# sos_v1.net
KiCad netlist of a schematic drawn in EAGLE
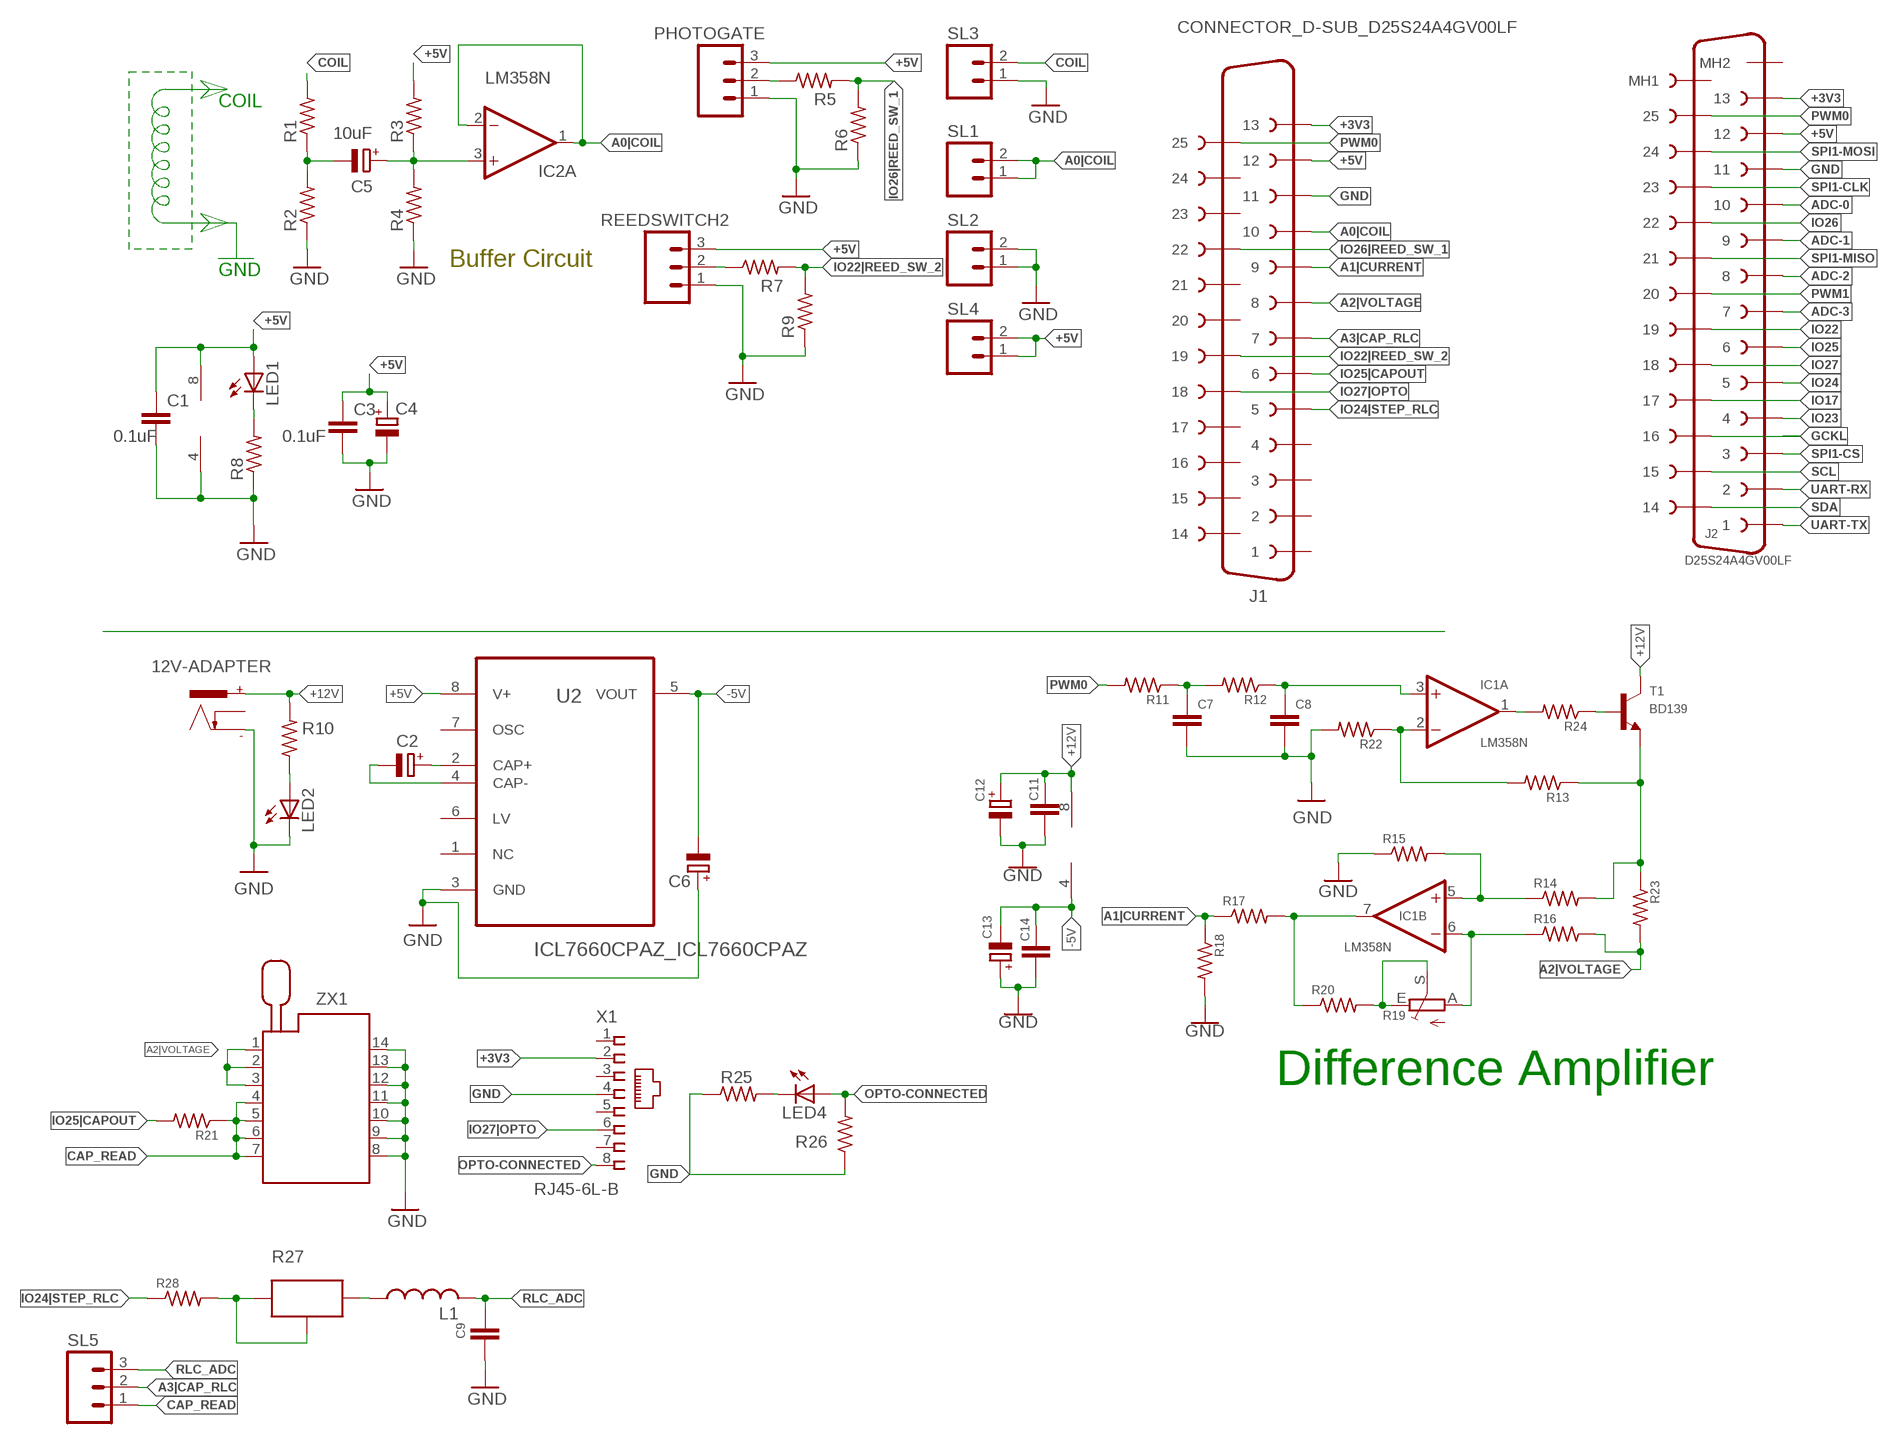
[diagram p0: schematic, sheet 1]

(export (version "E")
  (design (tool "Eeschema 10.0.6"))
  (components
    (comp (ref "12V-ADAPTER")
      (value "POWER_CON")
      (footprint "eagle-import:NEB21R")
      (libsource (lib "eagle-import") (part "POWER_CON"))
    )
    (comp (ref "C1")
      (value "0.1uF")
      (footprint "eagle-import:C025-025X050")
      (libsource (lib "eagle-import") (part "C-EU025-025X050"))
    )
    (comp (ref "C2")
      (value "CPOL-EUTT2D5")
      (footprint "eagle-import:TT2D5")
      (libsource (lib "eagle-import") (part "CPOL-EUTT2D5"))
    )
    (comp (ref "C3")
      (value "0.1uF")
      (footprint "eagle-import:C025-025X050")
      (libsource (lib "eagle-import") (part "C-EU025-025X050"))
    )
    (comp (ref "C4")
      (value "CPOL-EUE2.5-6")
      (footprint "eagle-import:E2,5-6")
      (libsource (lib "eagle-import") (part "CPOL-EUE2.5-6"))
    )
    (comp (ref "C5")
      (value "10uF")
      (footprint "eagle-import:E2,5-6")
      (libsource (lib "eagle-import") (part "CPOL-EUE2.5-6"))
    )
    (comp (ref "C6")
      (value "CPOL-EUTT2D5")
      (footprint "eagle-import:TT2D5")
      (libsource (lib "eagle-import") (part "CPOL-EUTT2D5"))
    )
    (comp (ref "C7")
      (value "C-EU025-025X050")
      (footprint "eagle-import:C025-025X050")
      (libsource (lib "eagle-import") (part "rcl_334_C-EU025-025X050"))
    )
    (comp (ref "C8")
      (value "C-EU025-025X050")
      (footprint "eagle-import:C025-025X050")
      (libsource (lib "eagle-import") (part "rcl_334_C-EU025-025X050"))
    )
    (comp (ref "C9")
      (value "C-EU025-025X050")
      (footprint "eagle-import:C025-025X050")
      (libsource (lib "eagle-import") (part "rcl_334_C-EU025-025X050"))
    )
    (comp (ref "C11")
      (value "C-EU025-025X050")
      (footprint "eagle-import:C025-025X050")
      (libsource (lib "eagle-import") (part "rcl_334_C-EU025-025X050"))
    )
    (comp (ref "C12")
      (value "CPOL-EUTT2D5")
      (footprint "eagle-import:TT2D5")
      (libsource (lib "eagle-import") (part "CPOL-EUTT2D5"))
    )
    (comp (ref "C13")
      (value "CPOL-EUTT2D5")
      (footprint "eagle-import:TT2D5")
      (libsource (lib "eagle-import") (part "CPOL-EUTT2D5"))
    )
    (comp (ref "C14")
      (value "C-EU025-025X050")
      (footprint "eagle-import:C025-025X050")
      (libsource (lib "eagle-import") (part "rcl_334_C-EU025-025X050"))
    )
    (comp (ref "IC1")
      (value "LM358N")
      (footprint "eagle-import:DIL08")
      (libsource (lib "eagle-import") (part "LM358N"))
    )
    (comp (ref "IC2")
      (value "LM358N")
      (footprint "eagle-import:DIL08")
      (libsource (lib "eagle-import") (part "LM358N"))
    )
    (comp (ref "J1")
      (value "CONNECTOR_D-SUB_D25S24A4GV00LF")
      (footprint "eagle-import:CONNECTOR_D-SUB_D25S24A4GV00LF")
      (fields (field (name "MANUFACTURER") "amphenol-icc") (field (name "MPN") "D25S24A4GV00LF"))
      (libsource (lib "eagle-import") (part "CONNECTOR_D-SUB_D25S24A4GV00LF"))
    )
    (comp (ref "J2")
      (value "D25S24A4GV00LF")
      (footprint "eagle-import:D25S24A4GV00LF")
      (fields (field (name "MANUFACTURER") "amphenol-icc"))
      (libsource (lib "eagle-import") (part "D25S24A4GV00LF"))
    )
    (comp (ref "L1")
      (value "L-USTJ3-U2")
      (footprint "eagle-import:TJ3-U2")
      (libsource (lib "eagle-import") (part "L-USTJ3-U2"))
    )
    (comp (ref "LED1")
      (value "LED3MM")
      (footprint "eagle-import:LED3MM")
      (libsource (lib "eagle-import") (part "LED3MM"))
    )
    (comp (ref "LED2")
      (value "LED3MM")
      (footprint "eagle-import:LED3MM")
      (libsource (lib "eagle-import") (part "LED3MM"))
    )
    (comp (ref "LED4")
      (value "LED3MM")
      (footprint "eagle-import:LED3MM")
      (libsource (lib "eagle-import") (part "LED3MM"))
    )
    (comp (ref "PHOTOGATE")
      (value "M03")
      (footprint "eagle-import:03P")
      (libsource (lib "eagle-import") (part "M03"))
    )
    (comp (ref "R1")
      (value "R-US_0204/7")
      (footprint "eagle-import:0204_7")
      (libsource (lib "eagle-import") (part "R-US_0204/7"))
    )
    (comp (ref "R2")
      (value "R-US_0204/7")
      (footprint "eagle-import:0204_7")
      (libsource (lib "eagle-import") (part "R-US_0204/7"))
    )
    (comp (ref "R3")
      (value "R-US_0204/7")
      (footprint "eagle-import:0204_7")
      (libsource (lib "eagle-import") (part "R-US_0204/7"))
    )
    (comp (ref "R4")
      (value "R-US_0204/7")
      (footprint "eagle-import:0204_7")
      (libsource (lib "eagle-import") (part "R-US_0204/7"))
    )
    (comp (ref "R5")
      (value "R-US_0204/7")
      (footprint "eagle-import:0204_7")
      (libsource (lib "eagle-import") (part "R-US_0204/7"))
    )
    (comp (ref "R6")
      (value "R-US_0204/7")
      (footprint "eagle-import:0204_7")
      (libsource (lib "eagle-import") (part "R-US_0204/7"))
    )
    (comp (ref "R7")
      (value "R-US_0204/7")
      (footprint "eagle-import:0204_7")
      (libsource (lib "eagle-import") (part "R-US_0204/7"))
    )
    (comp (ref "R8")
      (value "R-US_0204/7")
      (footprint "eagle-import:0204_7")
      (libsource (lib "eagle-import") (part "R-US_0204/7"))
    )
    (comp (ref "R9")
      (value "R-US_0204/7")
      (footprint "eagle-import:0204_7")
      (libsource (lib "eagle-import") (part "R-US_0204/7"))
    )
    (comp (ref "R10")
      (value "R-US_0204/7")
      (footprint "eagle-import:0204_7")
      (libsource (lib "eagle-import") (part "R-US_0204/7"))
    )
    (comp (ref "R11")
      (value "R-US_0204/7")
      (footprint "eagle-import:0204_7")
      (libsource (lib "eagle-import") (part "R-US_0204/7"))
    )
    (comp (ref "R12")
      (value "R-US_0204/7")
      (footprint "eagle-import:0204_7")
      (libsource (lib "eagle-import") (part "R-US_0204/7"))
    )
    (comp (ref "R13")
      (value "R-US_0204/7")
      (footprint "eagle-import:0204_7")
      (libsource (lib "eagle-import") (part "R-US_0204/7"))
    )
    (comp (ref "R14")
      (value "R-US_0204/7")
      (footprint "eagle-import:0204_7")
      (libsource (lib "eagle-import") (part "R-US_0204/7"))
    )
    (comp (ref "R15")
      (value "R-US_0204/7")
      (footprint "eagle-import:0204_7")
      (libsource (lib "eagle-import") (part "R-US_0204/7"))
    )
    (comp (ref "R16")
      (value "R-US_0204/7")
      (footprint "eagle-import:0204_7")
      (libsource (lib "eagle-import") (part "R-US_0204/7"))
    )
    (comp (ref "R17")
      (value "R-US_0204/7")
      (footprint "eagle-import:0204_7")
      (libsource (lib "eagle-import") (part "R-US_0204/7"))
    )
    (comp (ref "R18")
      (value "R-US_0204/7")
      (footprint "eagle-import:0204_7")
      (libsource (lib "eagle-import") (part "R-US_0204/7"))
    )
    (comp (ref "R19")
      (value "TRIM_EU-RJ9W")
      (footprint "eagle-import:RJ9W")
      (libsource (lib "eagle-import") (part "TRIM_EU-RJ9W"))
    )
    (comp (ref "R20")
      (value "R-US_0204/7")
      (footprint "eagle-import:0204_7")
      (libsource (lib "eagle-import") (part "R-US_0204/7"))
    )
    (comp (ref "R21")
      (value "R-US_0204/7")
      (footprint "eagle-import:0204_7")
      (libsource (lib "eagle-import") (part "R-US_0204/7"))
    )
    (comp (ref "R22")
      (value "R-US_0204/7")
      (footprint "eagle-import:0204_7")
      (libsource (lib "eagle-import") (part "R-US_0204/7"))
    )
    (comp (ref "R23")
      (value "R-US_0207/10")
      (footprint "eagle-import:0207_10")
      (libsource (lib "eagle-import") (part "R-US_0207/10"))
    )
    (comp (ref "R24")
      (value "R-US_0204/7")
      (footprint "eagle-import:0204_7")
      (libsource (lib "eagle-import") (part "R-US_0204/7"))
    )
    (comp (ref "R25")
      (value "R-US_0204/7")
      (footprint "eagle-import:0204_7")
      (libsource (lib "eagle-import") (part "R-US_0204/7"))
    )
    (comp (ref "R26")
      (value "R-US_0204/7")
      (footprint "eagle-import:0204_7")
      (libsource (lib "eagle-import") (part "R-US_0204/7"))
    )
    (comp (ref "R27")
      (value "POTNORMAL")
      (footprint "eagle-import:RJ9W")
      (libsource (lib "eagle-import") (part "POTNORMAL"))
    )
    (comp (ref "R28")
      (value "R-US_0207/10")
      (footprint "eagle-import:0207_10")
      (libsource (lib "eagle-import") (part "R-US_0207/10"))
    )
    (comp (ref "REEDSWITCH2")
      (value "M03")
      (footprint "eagle-import:03P")
      (libsource (lib "eagle-import") (part "M03"))
    )
    (comp (ref "SL1")
      (value "M02")
      (footprint "eagle-import:02P")
      (libsource (lib "eagle-import") (part "M02"))
    )
    (comp (ref "SL2")
      (value "M02")
      (footprint "eagle-import:02P")
      (libsource (lib "eagle-import") (part "M02"))
    )
    (comp (ref "SL3")
      (value "M02")
      (footprint "eagle-import:02P")
      (libsource (lib "eagle-import") (part "M02"))
    )
    (comp (ref "SL4")
      (value "M02")
      (footprint "eagle-import:02P")
      (libsource (lib "eagle-import") (part "M02"))
    )
    (comp (ref "SL5")
      (value "M03")
      (footprint "eagle-import:03P")
      (libsource (lib "eagle-import") (part "M03"))
    )
    (comp (ref "T1")
      (value "BD139")
      (footprint "eagle-import:TO126")
      (libsource (lib "eagle-import") (part "BD139"))
    )
    (comp (ref "U2")
      (value "ICL7660CPAZ_ICL7660CPAZ")
      (footprint "eagle-import:ICL7660CPAZ_DIP254P762X533-8")
      (fields (field (name "MF") "Renesas Electronics") (field (name "MP") "ICL7660CPAZ"))
      (libsource (lib "eagle-import") (part "ICL7660CPAZ_ICL7660CPAZ"))
    )
    (comp (ref "X1")
      (value "RJ45-6L-B")
      (footprint "eagle-import:RJ45-NO-SHIELD")
      (libsource (lib "eagle-import") (part "RJ45-6L-B"))
    )
    (comp (ref "ZX1")
      (value "214-3339-00-0602J")
      (footprint "eagle-import:214-3339-00-0602J")
      (fields (field (name "MF") "3M"))
      (libsource (lib "eagle-import") (part "214-3339-00-0602J"))
    )
  )
  (nets
    (net (code "1") (name "+3V3") (class "Default")
      (node (ref "J1") (pin "P$13") (pinfunction "13_P$13") (pintype "passive"))
      (node (ref "J2") (pin "13") (pinfunction "13_13") (pintype "passive"))
      (node (ref "X1") (pin "2") (pinfunction "2_2") (pintype "passive"))
    )
    (net (code "2") (name "+5V") (class "Default")
      (node (ref "C1") (pin "1") (pinfunction "1_1") (pintype "passive"))
      (node (ref "C3") (pin "1") (pinfunction "1_1") (pintype "passive"))
      (node (ref "C4") (pin "+") (pinfunction "+_+") (pintype "passive"))
      (node (ref "IC2") (pin "8") (pinfunction "V+_8") (pintype "power_in"))
      (node (ref "J1") (pin "P$14") (pinfunction "12_P$14") (pintype "passive"))
      (node (ref "J2") (pin "12") (pinfunction "12_12") (pintype "passive"))
      (node (ref "LED1") (pin "A") (pinfunction "A_A") (pintype "passive"))
      (node (ref "PHOTOGATE") (pin "3") (pinfunction "3_3") (pintype "passive"))
      (node (ref "R3") (pin "2") (pinfunction "2_2") (pintype "passive"))
      (node (ref "REEDSWITCH2") (pin "3") (pinfunction "3_3") (pintype "passive"))
      (node (ref "SL4") (pin "1") (pinfunction "1_1") (pintype "passive"))
      (node (ref "SL4") (pin "2") (pinfunction "2_2") (pintype "passive"))
      (node (ref "U2") (pin "8") (pinfunction "V+_8") (pintype "power_in"))
    )
    (net (code "3") (name "+12V") (class "Default")
      (node (ref "12V-ADAPTER") (pin "+") (pinfunction "+_+") (pintype "passive"))
      (node (ref "C11") (pin "1") (pinfunction "1_1") (pintype "passive"))
      (node (ref "C12") (pin "+") (pinfunction "+_+") (pintype "passive"))
      (node (ref "IC1") (pin "8") (pinfunction "V+_8") (pintype "power_in"))
      (node (ref "R10") (pin "2") (pinfunction "2_2") (pintype "passive"))
      (node (ref "T1") (pin "2") (pinfunction "C_2") (pintype "passive"))
    )
    (net (code "4") (name "-5V") (class "Default")
      (node (ref "C13") (pin "-") (pinfunction "-_-") (pintype "passive"))
      (node (ref "C14") (pin "1") (pinfunction "1_1") (pintype "passive"))
      (node (ref "C6") (pin "-") (pinfunction "-_-") (pintype "passive"))
      (node (ref "IC1") (pin "4") (pinfunction "V-_4") (pintype "power_in"))
      (node (ref "U2") (pin "5") (pinfunction "VOUT_5") (pintype "output"))
    )
    (net (code "5") (name "/MH1") (class "Default")
      (node (ref "J2") (pin "MH1") (pinfunction "MH1_MH1") (pintype "power_in"))
    )
    (net (code "6") (name "/MH2") (class "Default")
      (node (ref "J2") (pin "MH2") (pinfunction "MH2_MH2") (pintype "power_in"))
    )
    (net (code "7") (name "A0|COIL") (class "Default")
      (node (ref "IC2") (pin "1") (pinfunction "OUT_1") (pintype "output"))
      (node (ref "IC2") (pin "2") (pinfunction "-IN_2") (pintype "input"))
      (node (ref "J1") (pin "P$16") (pinfunction "10_P$16") (pintype "passive"))
      (node (ref "SL1") (pin "1") (pinfunction "1_1") (pintype "passive"))
      (node (ref "SL1") (pin "2") (pinfunction "2_2") (pintype "passive"))
    )
    (net (code "8") (name "A1|CURRENT") (class "Default")
      (node (ref "J1") (pin "P$17") (pinfunction "9_P$17") (pintype "passive"))
      (node (ref "R17") (pin "1") (pinfunction "1_1") (pintype "passive"))
      (node (ref "R18") (pin "1") (pinfunction "1_1") (pintype "passive"))
    )
    (net (code "9") (name "A2|VOLTAGE") (class "Default")
      (node (ref "J1") (pin "P$18") (pinfunction "8_P$18") (pintype "passive"))
      (node (ref "R16") (pin "2") (pinfunction "2_2") (pintype "passive"))
      (node (ref "R23") (pin "2") (pinfunction "2_2") (pintype "passive"))
      (node (ref "ZX1") (pin "1") (pinfunction "1_1") (pintype "passive"))
      (node (ref "ZX1") (pin "2") (pinfunction "2_2") (pintype "passive"))
      (node (ref "ZX1") (pin "3") (pinfunction "3_3") (pintype "passive"))
    )
    (net (code "10") (name "A3|CAP_RLC") (class "Default")
      (node (ref "J1") (pin "P$19") (pinfunction "7_P$19") (pintype "passive"))
      (node (ref "SL5") (pin "2") (pinfunction "2_2") (pintype "passive"))
    )
    (net (code "11") (name "ADC-0") (class "Default")
      (node (ref "J2") (pin "10") (pinfunction "10_10") (pintype "passive"))
    )
    (net (code "12") (name "ADC-1") (class "Default")
      (node (ref "J2") (pin "9") (pinfunction "9_9") (pintype "passive"))
    )
    (net (code "13") (name "ADC-2") (class "Default")
      (node (ref "J2") (pin "8") (pinfunction "8_8") (pintype "passive"))
    )
    (net (code "14") (name "ADC-3") (class "Default")
      (node (ref "J2") (pin "7") (pinfunction "7_7") (pintype "passive"))
    )
    (net (code "15") (name "CAP_READ") (class "Default")
      (node (ref "R21") (pin "1") (pinfunction "1_1") (pintype "passive"))
      (node (ref "SL5") (pin "1") (pinfunction "1_1") (pintype "passive"))
      (node (ref "ZX1") (pin "4") (pinfunction "4_4") (pintype "passive"))
      (node (ref "ZX1") (pin "5") (pinfunction "5_5") (pintype "passive"))
      (node (ref "ZX1") (pin "6") (pinfunction "6_6") (pintype "passive"))
      (node (ref "ZX1") (pin "7") (pinfunction "7_7") (pintype "passive"))
    )
    (net (code "16") (name "COIL") (class "Default")
      (node (ref "R1") (pin "2") (pinfunction "2_2") (pintype "passive"))
      (node (ref "SL3") (pin "2") (pinfunction "2_2") (pintype "passive"))
    )
    (net (code "17") (name "GCKL") (class "Default")
      (node (ref "J2") (pin "16") (pinfunction "16_16") (pintype "passive"))
    )
    (net (code "18") (name "GND") (class "Default")
      (node (ref "12V-ADAPTER") (pin "-") (pinfunction "-_-") (pintype "passive"))
      (node (ref "C1") (pin "2") (pinfunction "2_2") (pintype "passive"))
      (node (ref "C11") (pin "2") (pinfunction "2_2") (pintype "passive"))
      (node (ref "C12") (pin "-") (pinfunction "-_-") (pintype "passive"))
      (node (ref "C13") (pin "+") (pinfunction "+_+") (pintype "passive"))
      (node (ref "C14") (pin "2") (pinfunction "2_2") (pintype "passive"))
      (node (ref "C3") (pin "2") (pinfunction "2_2") (pintype "passive"))
      (node (ref "C4") (pin "-") (pinfunction "-_-") (pintype "passive"))
      (node (ref "C6") (pin "+") (pinfunction "+_+") (pintype "passive"))
      (node (ref "C7") (pin "2") (pinfunction "2_2") (pintype "passive"))
      (node (ref "C8") (pin "2") (pinfunction "2_2") (pintype "passive"))
      (node (ref "C9") (pin "2") (pinfunction "2_2") (pintype "passive"))
      (node (ref "IC2") (pin "4") (pinfunction "V-_4") (pintype "power_in"))
      (node (ref "J1") (pin "P$15") (pinfunction "11_P$15") (pintype "passive"))
      (node (ref "J2") (pin "11") (pinfunction "11_11") (pintype "passive"))
      (node (ref "LED2") (pin "K") (pinfunction "C_K") (pintype "passive"))
      (node (ref "PHOTOGATE") (pin "1") (pinfunction "1_1") (pintype "passive"))
      (node (ref "R15") (pin "1") (pinfunction "1_1") (pintype "passive"))
      (node (ref "R18") (pin "2") (pinfunction "2_2") (pintype "passive"))
      (node (ref "R2") (pin "1") (pinfunction "1_1") (pintype "passive"))
      (node (ref "R22") (pin "2") (pinfunction "2_2") (pintype "passive"))
      (node (ref "R25") (pin "1") (pinfunction "1_1") (pintype "passive"))
      (node (ref "R26") (pin "1") (pinfunction "1_1") (pintype "passive"))
      (node (ref "R4") (pin "1") (pinfunction "1_1") (pintype "passive"))
      (node (ref "R6") (pin "1") (pinfunction "1_1") (pintype "passive"))
      (node (ref "R8") (pin "1") (pinfunction "1_1") (pintype "passive"))
      (node (ref "R9") (pin "1") (pinfunction "1_1") (pintype "passive"))
      (node (ref "REEDSWITCH2") (pin "1") (pinfunction "1_1") (pintype "passive"))
      (node (ref "SL2") (pin "1") (pinfunction "1_1") (pintype "passive"))
      (node (ref "SL2") (pin "2") (pinfunction "2_2") (pintype "passive"))
      (node (ref "SL3") (pin "1") (pinfunction "1_1") (pintype "passive"))
      (node (ref "U2") (pin "3") (pinfunction "GND_3") (pintype "passive"))
      (node (ref "X1") (pin "4") (pinfunction "4_4") (pintype "passive"))
      (node (ref "ZX1") (pin "10") (pinfunction "10_10") (pintype "passive"))
      (node (ref "ZX1") (pin "11") (pinfunction "11_11") (pintype "passive"))
      (node (ref "ZX1") (pin "12") (pinfunction "12_12") (pintype "passive"))
      (node (ref "ZX1") (pin "13") (pinfunction "13_13") (pintype "passive"))
      (node (ref "ZX1") (pin "14") (pinfunction "14_14") (pintype "passive"))
      (node (ref "ZX1") (pin "8") (pinfunction "8_8") (pintype "passive"))
      (node (ref "ZX1") (pin "9") (pinfunction "9_9") (pintype "passive"))
    )
    (net (code "19") (name "IO17") (class "Default")
      (node (ref "J2") (pin "17") (pinfunction "17_17") (pintype "passive"))
    )
    (net (code "20") (name "IO22") (class "Default")
      (node (ref "J2") (pin "19") (pinfunction "19_19") (pintype "passive"))
    )
    (net (code "21") (name "IO22|REED_SW_2") (class "Default")
      (node (ref "J1") (pin "P$7") (pinfunction "19_P$7") (pintype "passive"))
      (node (ref "R7") (pin "2") (pinfunction "2_2") (pintype "passive"))
      (node (ref "R9") (pin "2") (pinfunction "2_2") (pintype "passive"))
    )
    (net (code "22") (name "IO23") (class "Default")
      (node (ref "J2") (pin "4") (pinfunction "4_4") (pintype "passive"))
    )
    (net (code "23") (name "IO24") (class "Default")
      (node (ref "J2") (pin "5") (pinfunction "5_5") (pintype "passive"))
    )
    (net (code "24") (name "IO24|STEP_RLC") (class "Default")
      (node (ref "J1") (pin "P$21") (pinfunction "5_P$21") (pintype "passive"))
      (node (ref "R28") (pin "1") (pinfunction "1_1") (pintype "passive"))
    )
    (net (code "25") (name "IO25") (class "Default")
      (node (ref "J2") (pin "6") (pinfunction "6_6") (pintype "passive"))
    )
    (net (code "26") (name "IO25|CAPOUT") (class "Default")
      (node (ref "J1") (pin "P$20") (pinfunction "6_P$20") (pintype "passive"))
      (node (ref "R21") (pin "2") (pinfunction "2_2") (pintype "passive"))
    )
    (net (code "27") (name "IO26") (class "Default")
      (node (ref "J2") (pin "22") (pinfunction "22_22") (pintype "passive"))
    )
    (net (code "28") (name "IO26|REED_SW_1") (class "Default")
      (node (ref "J1") (pin "P$4") (pinfunction "22_P$4") (pintype "passive"))
      (node (ref "R5") (pin "2") (pinfunction "2_2") (pintype "passive"))
      (node (ref "R6") (pin "2") (pinfunction "2_2") (pintype "passive"))
    )
    (net (code "29") (name "IO27") (class "Default")
      (node (ref "J2") (pin "18") (pinfunction "18_18") (pintype "passive"))
    )
    (net (code "30") (name "IO27|OPTO") (class "Default")
      (node (ref "J1") (pin "P$8") (pinfunction "18_P$8") (pintype "passive"))
      (node (ref "X1") (pin "6") (pinfunction "6_6") (pintype "passive"))
    )
    (net (code "31") (name "Net-(C5-Pad-)") (class "Default")
      (node (ref "C5") (pin "-") (pinfunction "-_-") (pintype "passive"))
      (node (ref "R1") (pin "1") (pinfunction "1_1") (pintype "passive"))
      (node (ref "R2") (pin "2") (pinfunction "2_2") (pintype "passive"))
    )
    (net (code "32") (name "Net-(C7-Pad1)") (class "Default")
      (node (ref "C7") (pin "1") (pinfunction "1_1") (pintype "passive"))
      (node (ref "R11") (pin "1") (pinfunction "1_1") (pintype "passive"))
      (node (ref "R12") (pin "2") (pinfunction "2_2") (pintype "passive"))
    )
    (net (code "33") (name "Net-(IC1A-+IN)") (class "Default")
      (node (ref "C8") (pin "1") (pinfunction "1_1") (pintype "passive"))
      (node (ref "IC1") (pin "3") (pinfunction "+IN_3") (pintype "input"))
      (node (ref "R12") (pin "1") (pinfunction "1_1") (pintype "passive"))
    )
    (net (code "34") (name "Net-(IC1A--IN)") (class "Default")
      (node (ref "IC1") (pin "2") (pinfunction "-IN_2") (pintype "input"))
      (node (ref "R13") (pin "2") (pinfunction "2_2") (pintype "passive"))
      (node (ref "R22") (pin "1") (pinfunction "1_1") (pintype "passive"))
    )
    (net (code "35") (name "Net-(IC1A-OUT)") (class "Default")
      (node (ref "IC1") (pin "1") (pinfunction "OUT_1") (pintype "output"))
      (node (ref "R24") (pin "2") (pinfunction "2_2") (pintype "passive"))
    )
    (net (code "36") (name "Net-(IC1B-+IN)") (class "Default")
      (node (ref "IC1") (pin "5") (pinfunction "+IN_5") (pintype "input"))
      (node (ref "R14") (pin "1") (pinfunction "1_1") (pintype "passive"))
      (node (ref "R15") (pin "2") (pinfunction "2_2") (pintype "passive"))
    )
    (net (code "37") (name "Net-(IC1B--IN)") (class "Default")
      (node (ref "IC1") (pin "6") (pinfunction "-IN_6") (pintype "input"))
      (node (ref "R16") (pin "1") (pinfunction "1_1") (pintype "passive"))
      (node (ref "R19") (pin "A") (pinfunction "A_A") (pintype "passive"))
    )
    (net (code "38") (name "Net-(IC1B-OUT)") (class "Default")
      (node (ref "IC1") (pin "7") (pinfunction "OUT_7") (pintype "output"))
      (node (ref "R17") (pin "2") (pinfunction "2_2") (pintype "passive"))
      (node (ref "R20") (pin "1") (pinfunction "1_1") (pintype "passive"))
    )
    (net (code "39") (name "Net-(IC2A-+IN)") (class "Default")
      (node (ref "C5") (pin "+") (pinfunction "+_+") (pintype "passive"))
      (node (ref "IC2") (pin "3") (pinfunction "+IN_3") (pintype "input"))
      (node (ref "R3") (pin "1") (pinfunction "1_1") (pintype "passive"))
      (node (ref "R4") (pin "2") (pinfunction "2_2") (pintype "passive"))
    )
    (net (code "40") (name "Net-(L1-Pad1)") (class "Default")
      (node (ref "L1") (pin "1") (pinfunction "1_1") (pintype "passive"))
      (node (ref "R27") (pin "A") (pinfunction "A_A") (pintype "passive"))
    )
    (net (code "41") (name "Net-(LED1-C)") (class "Default")
      (node (ref "LED1") (pin "K") (pinfunction "C_K") (pintype "passive"))
      (node (ref "R8") (pin "2") (pinfunction "2_2") (pintype "passive"))
    )
    (net (code "42") (name "Net-(LED2-PadA)") (class "Default")
      (node (ref "LED2") (pin "A") (pinfunction "A_A") (pintype "passive"))
      (node (ref "R10") (pin "1") (pinfunction "1_1") (pintype "passive"))
    )
    (net (code "43") (name "Net-(LED4-C)") (class "Default")
      (node (ref "LED4") (pin "K") (pinfunction "C_K") (pintype "passive"))
      (node (ref "R25") (pin "2") (pinfunction "2_2") (pintype "passive"))
    )
    (net (code "44") (name "Net-(PHOTOGATE-Pad2)") (class "Default")
      (node (ref "PHOTOGATE") (pin "2") (pinfunction "2_2") (pintype "passive"))
      (node (ref "R5") (pin "1") (pinfunction "1_1") (pintype "passive"))
    )
    (net (code "45") (name "Net-(R7-Pad1)") (class "Default")
      (node (ref "R7") (pin "1") (pinfunction "1_1") (pintype "passive"))
      (node (ref "REEDSWITCH2") (pin "2") (pinfunction "2_2") (pintype "passive"))
    )
    (net (code "46") (name "Net-(R19-PadE)") (class "Default")
      (node (ref "R19") (pin "E") (pinfunction "E_E") (pintype "passive"))
      (node (ref "R19") (pin "S") (pinfunction "S_S") (pintype "passive"))
      (node (ref "R20") (pin "2") (pinfunction "2_2") (pintype "passive"))
    )
    (net (code "47") (name "Net-(R27-PadE)") (class "Default")
      (node (ref "R27") (pin "E") (pinfunction "E_E") (pintype "passive"))
      (node (ref "R27") (pin "S") (pinfunction "S_S") (pintype "passive"))
      (node (ref "R28") (pin "2") (pinfunction "2_2") (pintype "passive"))
    )
    (net (code "48") (name "Net-(T1-B)") (class "Default")
      (node (ref "R24") (pin "1") (pinfunction "1_1") (pintype "passive"))
      (node (ref "T1") (pin "3") (pinfunction "B_3") (pintype "passive"))
    )
    (net (code "49") (name "Net-(T1-E)") (class "Default")
      (node (ref "R13") (pin "1") (pinfunction "1_1") (pintype "passive"))
      (node (ref "R14") (pin "2") (pinfunction "2_2") (pintype "passive"))
      (node (ref "R23") (pin "1") (pinfunction "1_1") (pintype "passive"))
      (node (ref "T1") (pin "1") (pinfunction "E_1") (pintype "passive"))
    )
    (net (code "50") (name "Net-(U2-CAP+)") (class "Default")
      (node (ref "C2") (pin "+") (pinfunction "+_+") (pintype "passive"))
      (node (ref "U2") (pin "2") (pinfunction "CAP+_2") (pintype "input"))
    )
    (net (code "51") (name "Net-(U2-CAP-)") (class "Default")
      (node (ref "C2") (pin "-") (pinfunction "-_-") (pintype "passive"))
      (node (ref "U2") (pin "4") (pinfunction "CAP-_4") (pintype "input"))
    )
    (net (code "52") (name "OPTO-CONNECTED") (class "Default")
      (node (ref "LED4") (pin "A") (pinfunction "A_A") (pintype "passive"))
      (node (ref "R26") (pin "2") (pinfunction "2_2") (pintype "passive"))
      (node (ref "X1") (pin "8") (pinfunction "8_8") (pintype "passive"))
    )
    (net (code "53") (name "PWM0") (class "Default")
      (node (ref "J1") (pin "P$1") (pinfunction "25_P$1") (pintype "passive"))
      (node (ref "J2") (pin "25") (pinfunction "25_25") (pintype "passive"))
      (node (ref "R11") (pin "2") (pinfunction "2_2") (pintype "passive"))
    )
    (net (code "54") (name "PWM1") (class "Default")
      (node (ref "J2") (pin "20") (pinfunction "20_20") (pintype "passive"))
    )
    (net (code "55") (name "RLC_ADC") (class "Default")
      (node (ref "C9") (pin "1") (pinfunction "1_1") (pintype "passive"))
      (node (ref "L1") (pin "2") (pinfunction "2_2") (pintype "passive"))
      (node (ref "SL5") (pin "3") (pinfunction "3_3") (pintype "passive"))
    )
    (net (code "56") (name "SCL") (class "Default")
      (node (ref "J2") (pin "15") (pinfunction "15_15") (pintype "passive"))
    )
    (net (code "57") (name "SDA") (class "Default")
      (node (ref "J2") (pin "14") (pinfunction "14_14") (pintype "passive"))
    )
    (net (code "58") (name "SPI1-CLK") (class "Default")
      (node (ref "J2") (pin "23") (pinfunction "23_23") (pintype "passive"))
    )
    (net (code "59") (name "SPI1-CS") (class "Default")
      (node (ref "J2") (pin "3") (pinfunction "3_3") (pintype "passive"))
    )
    (net (code "60") (name "SPI1-MISO") (class "Default")
      (node (ref "J2") (pin "21") (pinfunction "21_21") (pintype "passive"))
    )
    (net (code "61") (name "SPI1-MOSI") (class "Default")
      (node (ref "J2") (pin "24") (pinfunction "24_24") (pintype "passive"))
    )
    (net (code "62") (name "UART-RX") (class "Default")
      (node (ref "J2") (pin "2") (pinfunction "2_2") (pintype "passive"))
    )
    (net (code "63") (name "UART-TX") (class "Default")
      (node (ref "J2") (pin "1") (pinfunction "1_1") (pintype "passive"))
    )
    (net (code "64") (name "unconnected-(12V-ADAPTER-PadC)") (class "Default")
      (node (ref "12V-ADAPTER") (pin "C") (pinfunction "C_C") (pintype "passive"))
    )
    (net (code "65") (name "unconnected-(J1-2-PadP$24)") (class "Default")
      (node (ref "J1") (pin "P$24") (pinfunction "2_P$24") (pintype "passive"))
    )
    (net (code "66") (name "unconnected-(J1-3-PadP$23)") (class "Default")
      (node (ref "J1") (pin "P$23") (pinfunction "3_P$23") (pintype "passive"))
    )
    (net (code "67") (name "unconnected-(J1-4-PadP$22)") (class "Default")
      (node (ref "J1") (pin "P$22") (pinfunction "4_P$22") (pintype "passive"))
    )
    (net (code "68") (name "unconnected-(J1-14-PadP$12)") (class "Default")
      (node (ref "J1") (pin "P$12") (pinfunction "14_P$12") (pintype "passive"))
    )
    (net (code "69") (name "unconnected-(J1-15-PadP$11)") (class "Default")
      (node (ref "J1") (pin "P$11") (pinfunction "15_P$11") (pintype "passive"))
    )
    (net (code "70") (name "unconnected-(J1-16-PadP$10)") (class "Default")
      (node (ref "J1") (pin "P$10") (pinfunction "16_P$10") (pintype "passive"))
    )
    (net (code "71") (name "unconnected-(J1-17-PadP$9)") (class "Default")
      (node (ref "J1") (pin "P$9") (pinfunction "17_P$9") (pintype "passive"))
    )
    (net (code "72") (name "unconnected-(J1-20-PadP$6)") (class "Default")
      (node (ref "J1") (pin "P$6") (pinfunction "20_P$6") (pintype "passive"))
    )
    (net (code "73") (name "unconnected-(J1-21-PadP$5)") (class "Default")
      (node (ref "J1") (pin "P$5") (pinfunction "21_P$5") (pintype "passive"))
    )
    (net (code "74") (name "unconnected-(J1-23-PadP$3)") (class "Default")
      (node (ref "J1") (pin "P$3") (pinfunction "23_P$3") (pintype "passive"))
    )
    (net (code "75") (name "unconnected-(J1-24-PadP$2)") (class "Default")
      (node (ref "J1") (pin "P$2") (pinfunction "24_P$2") (pintype "passive"))
    )
    (net (code "76") (name "unconnected-(J1-Pad1)") (class "Default")
      (node (ref "J1") (pin "1") (pinfunction "1_1") (pintype "passive"))
    )
    (net (code "77") (name "unconnected-(U2-LV-Pad6)") (class "Default")
      (node (ref "U2") (pin "6") (pinfunction "LV_6") (pintype "passive"))
    )
    (net (code "78") (name "unconnected-(U2-NC-Pad1)") (class "Default")
      (node (ref "U2") (pin "1") (pinfunction "NC_1") (pintype "no_connect"))
    )
    (net (code "79") (name "unconnected-(U2-OSC-Pad7)") (class "Default")
      (node (ref "U2") (pin "7") (pinfunction "OSC_7") (pintype "input"))
    )
    (net (code "80") (name "unconnected-(X1-Pad1)") (class "Default")
      (node (ref "X1") (pin "1") (pinfunction "1_1") (pintype "passive"))
    )
    (net (code "81") (name "unconnected-(X1-Pad3)") (class "Default")
      (node (ref "X1") (pin "3") (pinfunction "3_3") (pintype "passive"))
    )
    (net (code "82") (name "unconnected-(X1-Pad5)") (class "Default")
      (node (ref "X1") (pin "5") (pinfunction "5_5") (pintype "passive"))
    )
    (net (code "83") (name "unconnected-(X1-Pad7)") (class "Default")
      (node (ref "X1") (pin "7") (pinfunction "7_7") (pintype "passive"))
    )
  )
)
